# TIA_SWITCHES.net
KiCad netlist of a schematic drawn in Altium Designer
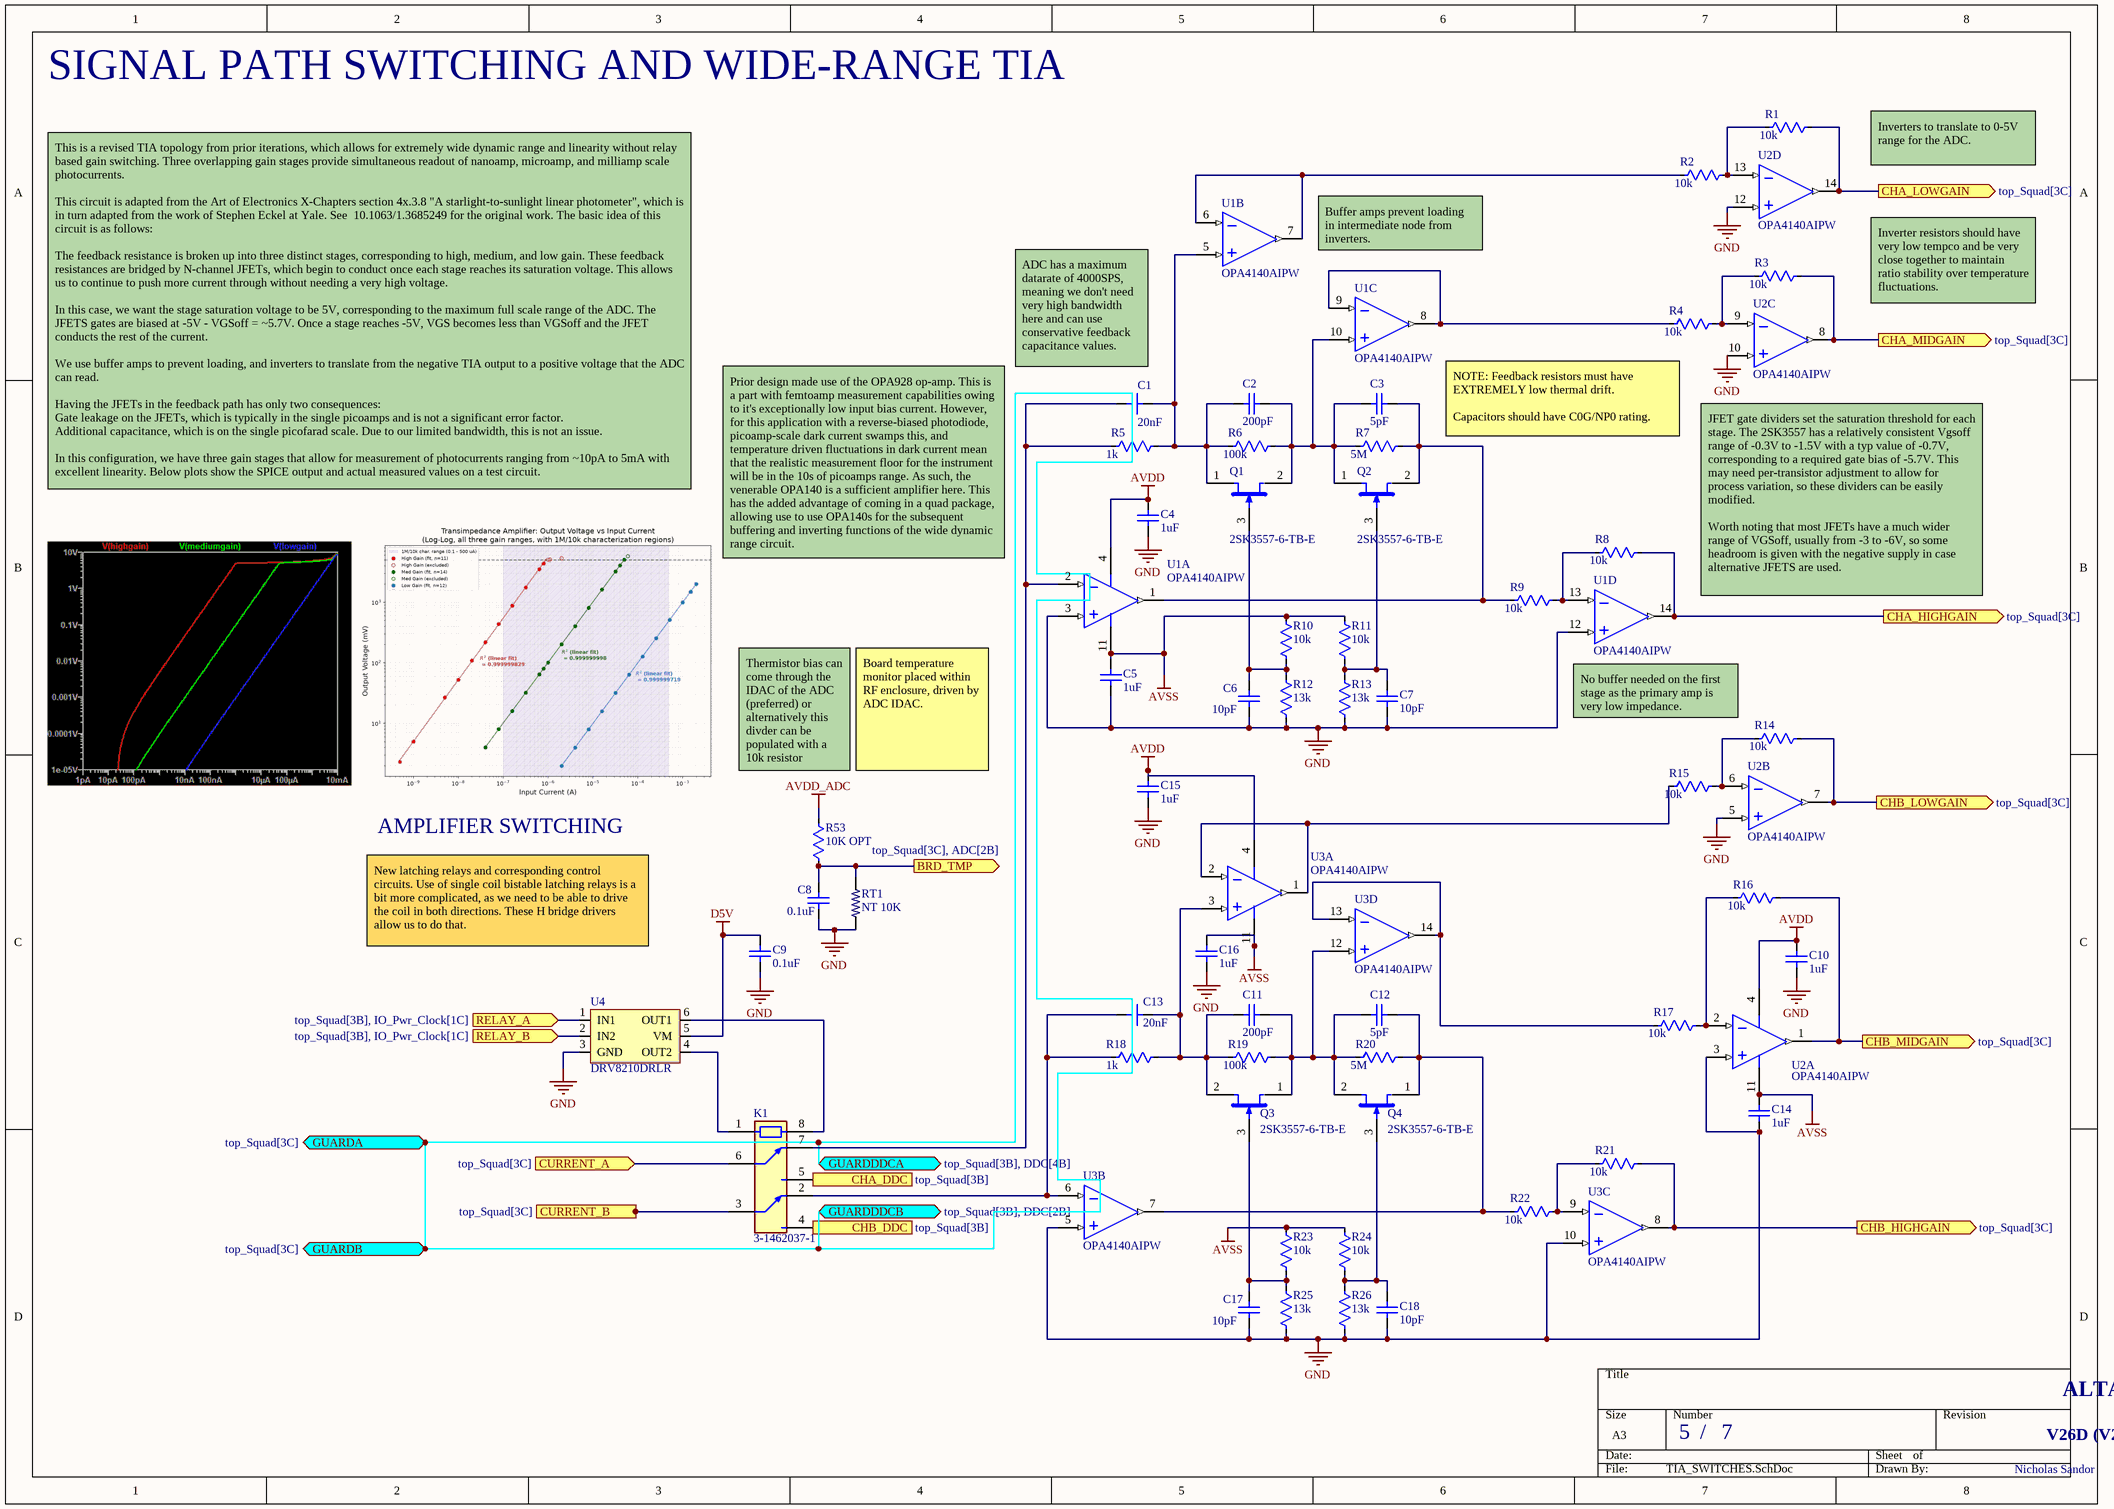
[diagram p0: TIA_SWITCHES.SchDoc]

(export (version "E")
  (design (tool "Eeschema 10.0.6"))
  (components
    (comp (ref "C1")
      (value "20nF")
      (footprint "CAP 1206 UNKNOWN")
      (description "Wurth Elektronik 885012008037 - Cap Ceramic 10pF 5% 50V NP0 1206")
      (fields (field (name "MF") "Wurth Elektronik") (field (name "MP") "885012008037"))
      (libsource (lib "ALTAIR_PD_Capacitors") (part "CAP"))
    )
    (comp (ref "C2")
      (value "200pF")
      (footprint "CAP 1206 UNKNOWN")
      (description "Wurth Elektronik 885012008037 - Cap Ceramic 10pF 5% 50V NP0 1206")
      (fields (field (name "MF") "Wurth Elektronik") (field (name "MP") "885012008037"))
      (libsource (lib "ALTAIR_PD_Capacitors") (part "CAP"))
    )
    (comp (ref "C3")
      (value "5pF")
      (footprint "CAP 1206 UNKNOWN")
      (description "Wurth Elektronik 885012008037 - Cap Ceramic 10pF 5% 50V NP0 1206")
      (fields (field (name "MF") "Wurth Elektronik") (field (name "MP") "885012008037"))
      (libsource (lib "ALTAIR_PD_Capacitors") (part "CAP"))
    )
    (comp (ref "C4")
      (value "1uF")
      (footprint "CAP 0603 IPC MID DENSITY")
      (description "Murata GRT188R61H105KE13D - Cap MLCC AEC-Q200 X5R 1uF 50V 0603")
      (fields (field (name "MF") "Murata") (field (name "MP") "GRT188R61H105KE13D"))
      (libsource (lib "ALTAIR_PD_Capacitors") (part "CAP"))
    )
    (comp (ref "C5")
      (value "1uF")
      (footprint "CAP 0603 IPC MID DENSITY")
      (description "Murata GRT188R61H105KE13D - Cap MLCC AEC-Q200 X5R 1uF 50V 0603")
      (fields (field (name "MF") "Murata") (field (name "MP") "GRT188R61H105KE13D"))
      (libsource (lib "ALTAIR_PD_Capacitors") (part "CAP"))
    )
    (comp (ref "C6")
      (value "10pF")
      (footprint "CAP 0603 IPC MID DENSITY MURATA")
      (description "Wurth Elektronik 885012008037 - Cap Ceramic 10pF 5% 50V NP0 1206")
      (fields (field (name "MF") "Wurth Elektronik") (field (name "MP") "885012008037"))
      (libsource (lib "ALTAIR_PD_Capacitors") (part "CAP"))
    )
    (comp (ref "C7")
      (value "10pF")
      (footprint "CAP 0603 IPC MID DENSITY MURATA")
      (description "Wurth Elektronik 885012008037 - Cap Ceramic 10pF 5% 50V NP0 1206")
      (fields (field (name "MF") "Wurth Elektronik") (field (name "MP") "885012008037"))
      (libsource (lib "ALTAIR_PD_Capacitors") (part "CAP"))
    )
    (comp (ref "C8")
      (value "0.1uF")
      (footprint "CAP 0603 IPC MID DENSITY")
      (description "Kemet C0603C104K5RACAUTO - Cap Ceramic 0.1uF 50V X7R 10% 0603 125C Paper T/R")
      (fields (field (name "MF") "Kemet") (field (name "MP") "C0603C104K5RACAUTO"))
      (libsource (lib "ALTAIR_PD_Capacitors") (part "CAP"))
    )
    (comp (ref "C9")
      (value "0.1uF")
      (footprint "CAP 0603 IPC MID DENSITY")
      (description "Kemet C0603C104K5RACAUTO - Cap Ceramic 0.1uF 50V X7R 10% 0603 125C Paper T/R")
      (fields (field (name "MF") "Kemet") (field (name "MP") "C0603C104K5RACAUTO"))
      (libsource (lib "ALTAIR_PD_Capacitors") (part "CAP"))
    )
    (comp (ref "C10")
      (value "1uF")
      (footprint "CAP 0603 IPC MID DENSITY")
      (description "Murata GRT188R61H105KE13D - Cap MLCC AEC-Q200 X5R 1uF 50V 0603")
      (fields (field (name "MF") "Murata") (field (name "MP") "GRT188R61H105KE13D"))
      (libsource (lib "ALTAIR_PD_Capacitors") (part "CAP"))
    )
    (comp (ref "C11")
      (value "200pF")
      (footprint "CAP 1206 UNKNOWN")
      (description "Wurth Elektronik 885012008037 - Cap Ceramic 10pF 5% 50V NP0 1206")
      (fields (field (name "MF") "Wurth Elektronik") (field (name "MP") "885012008037"))
      (libsource (lib "ALTAIR_PD_Capacitors") (part "CAP"))
    )
    (comp (ref "C12")
      (value "5pF")
      (footprint "CAP 1206 UNKNOWN")
      (description "Wurth Elektronik 885012008037 - Cap Ceramic 10pF 5% 50V NP0 1206")
      (fields (field (name "MF") "Wurth Elektronik") (field (name "MP") "885012008037"))
      (libsource (lib "ALTAIR_PD_Capacitors") (part "CAP"))
    )
    (comp (ref "C13")
      (value "20nF")
      (footprint "CAP 1206 UNKNOWN")
      (description "Wurth Elektronik 885012008037 - Cap Ceramic 10pF 5% 50V NP0 1206")
      (fields (field (name "MF") "Wurth Elektronik") (field (name "MP") "885012008037"))
      (libsource (lib "ALTAIR_PD_Capacitors") (part "CAP"))
    )
    (comp (ref "C14")
      (value "1uF")
      (footprint "CAP 0603 IPC MID DENSITY")
      (description "Murata GRT188R61H105KE13D - Cap MLCC AEC-Q200 X5R 1uF 50V 0603")
      (fields (field (name "MF") "Murata") (field (name "MP") "GRT188R61H105KE13D"))
      (libsource (lib "ALTAIR_PD_Capacitors") (part "CAP"))
    )
    (comp (ref "C15")
      (value "1uF")
      (footprint "CAP 0603 IPC MID DENSITY")
      (description "Murata GRT188R61H105KE13D - Cap MLCC AEC-Q200 X5R 1uF 50V 0603")
      (fields (field (name "MF") "Murata") (field (name "MP") "GRT188R61H105KE13D"))
      (libsource (lib "ALTAIR_PD_Capacitors") (part "CAP"))
    )
    (comp (ref "C16")
      (value "1uF")
      (footprint "CAP 0603 IPC MID DENSITY")
      (description "Murata GRT188R61H105KE13D - Cap MLCC AEC-Q200 X5R 1uF 50V 0603")
      (fields (field (name "MF") "Murata") (field (name "MP") "GRT188R61H105KE13D"))
      (libsource (lib "ALTAIR_PD_Capacitors") (part "CAP"))
    )
    (comp (ref "C17")
      (value "10pF")
      (footprint "CAP 0603 IPC MID DENSITY MURATA")
      (description "Wurth Elektronik 885012008037 - Cap Ceramic 10pF 5% 50V NP0 1206")
      (fields (field (name "MF") "Wurth Elektronik") (field (name "MP") "885012008037"))
      (libsource (lib "ALTAIR_PD_Capacitors") (part "CAP"))
    )
    (comp (ref "C18")
      (value "10pF")
      (footprint "CAP 0603 IPC MID DENSITY MURATA")
      (description "Wurth Elektronik 885012008037 - Cap Ceramic 10pF 5% 50V NP0 1206")
      (fields (field (name "MF") "Wurth Elektronik") (field (name "MP") "885012008037"))
      (libsource (lib "ALTAIR_PD_Capacitors") (part "CAP"))
    )
    (comp (ref "K1")
      (value "3-1462037-1")
      (footprint "RELAY_3-1462037-1")
      (fields (field (name "MF") "TE Connectivity"))
      (libsource (lib "ALTAIR_PD_Switches") (part "3-1462037-1"))
    )
    (comp (ref "Q1")
      (value "2SK3557-6-TB-E")
      (footprint "ONSC-CP-3-318AN_A_V")
      (description "N-Channel JFET, 15 V, 10 to 20 mA, 35 mS, 3-Pin CP, Pb-Free, Tape and Reel")
      (fields (field (name "MANUFACTURER") "On Semiconductor"))
      (libsource (lib "ALTAIR_PD_FETs") (part "CMP-1062-00010-1"))
    )
    (comp (ref "Q2")
      (value "2SK3557-6-TB-E")
      (footprint "ONSC-CP-3-318AN_A_V")
      (description "N-Channel JFET, 15 V, 10 to 20 mA, 35 mS, 3-Pin CP, Pb-Free, Tape and Reel")
      (fields (field (name "MANUFACTURER") "On Semiconductor"))
      (libsource (lib "ALTAIR_PD_FETs") (part "CMP-1062-00010-1"))
    )
    (comp (ref "Q3")
      (value "2SK3557-6-TB-E")
      (footprint "ONSC-CP-3-318AN_A_V")
      (description "N-Channel JFET, 15 V, 10 to 20 mA, 35 mS, 3-Pin CP, Pb-Free, Tape and Reel")
      (fields (field (name "MANUFACTURER") "On Semiconductor"))
      (libsource (lib "ALTAIR_PD_FETs") (part "CMP-1062-00010-1"))
    )
    (comp (ref "Q4")
      (value "2SK3557-6-TB-E")
      (footprint "ONSC-CP-3-318AN_A_V")
      (description "N-Channel JFET, 15 V, 10 to 20 mA, 35 mS, 3-Pin CP, Pb-Free, Tape and Reel")
      (fields (field (name "MANUFACTURER") "On Semiconductor"))
      (libsource (lib "ALTAIR_PD_FETs") (part "CMP-1062-00010-1"))
    )
    (comp (ref "R1")
      (value "10k")
      (footprint "RES 0603 IPC MID DENSITY")
      (description "Vishay TNPV12061M00BYEN - Res 1MOhm 0.1% 1/4W SMD 1206")
      (fields (field (name "MF") "Vishay Dale") (field (name "MP") "TNPV12061M00BYEN"))
      (libsource (lib "ALTAIR_PD_Resistors") (part "RES"))
    )
    (comp (ref "R2")
      (value "10k")
      (footprint "RES 0603 IPC MID DENSITY")
      (description "Vishay TNPV12061M00BYEN - Res 1MOhm 0.1% 1/4W SMD 1206")
      (fields (field (name "MF") "Vishay Dale") (field (name "MP") "TNPV12061M00BYEN"))
      (libsource (lib "ALTAIR_PD_Resistors") (part "RES"))
    )
    (comp (ref "R3")
      (value "10k")
      (footprint "RES 0603 IPC MID DENSITY")
      (description "Vishay TNPV12061M00BYEN - Res 1MOhm 0.1% 1/4W SMD 1206")
      (fields (field (name "MF") "Vishay Dale") (field (name "MP") "TNPV12061M00BYEN"))
      (libsource (lib "ALTAIR_PD_Resistors") (part "RES"))
    )
    (comp (ref "R4")
      (value "10k")
      (footprint "RES 0603 IPC MID DENSITY")
      (description "Vishay TNPV12061M00BYEN - Res 1MOhm 0.1% 1/4W SMD 1206")
      (fields (field (name "MF") "Vishay Dale") (field (name "MP") "TNPV12061M00BYEN"))
      (libsource (lib "ALTAIR_PD_Resistors") (part "RES"))
    )
    (comp (ref "R5")
      (value "1k")
      (footprint "RES 1206 IPC MID DENSITY")
      (description "Vishay TNPV12061M00BYEN - Res 1MOhm 0.1% 1/4W SMD 1206")
      (fields (field (name "MF") "Vishay Dale") (field (name "MP") "TNPV12061M00BYEN"))
      (libsource (lib "ALTAIR_PD_Resistors") (part "RES"))
    )
    (comp (ref "R6")
      (value "100k")
      (footprint "RES 1206 IPC MID DENSITY")
      (description "Vishay TNPV12061M00BYEN - Res 1MOhm 0.1% 1/4W SMD 1206")
      (fields (field (name "MF") "Vishay Dale") (field (name "MP") "TNPV12061M00BYEN"))
      (libsource (lib "ALTAIR_PD_Resistors") (part "RES"))
    )
    (comp (ref "R7")
      (value "5M")
      (footprint "RES 1206 IPC MID DENSITY")
      (description "Vishay TNPV12061M00BYEN - Res 1MOhm 0.1% 1/4W SMD 1206")
      (fields (field (name "MF") "Vishay Dale") (field (name "MP") "TNPV12061M00BYEN"))
      (libsource (lib "ALTAIR_PD_Resistors") (part "RES"))
    )
    (comp (ref "R8")
      (value "10k")
      (footprint "RES 0603 IPC MID DENSITY")
      (description "Vishay TNPV12061M00BYEN - Res 1MOhm 0.1% 1/4W SMD 1206")
      (fields (field (name "MF") "Vishay Dale") (field (name "MP") "TNPV12061M00BYEN"))
      (libsource (lib "ALTAIR_PD_Resistors") (part "RES"))
    )
    (comp (ref "R9")
      (value "10k")
      (footprint "RES 0603 IPC MID DENSITY")
      (description "Vishay TNPV12061M00BYEN - Res 1MOhm 0.1% 1/4W SMD 1206")
      (fields (field (name "MF") "Vishay Dale") (field (name "MP") "TNPV12061M00BYEN"))
      (libsource (lib "ALTAIR_PD_Resistors") (part "RES"))
    )
    (comp (ref "R10")
      (value "10k")
      (footprint "RES 0603 IPC MID DENSITY")
      (description "Vishay TNPV12061M00BYEN - Res 1MOhm 0.1% 1/4W SMD 1206")
      (fields (field (name "MF") "Vishay Dale") (field (name "MP") "TNPV12061M00BYEN"))
      (libsource (lib "ALTAIR_PD_Resistors") (part "RES"))
    )
    (comp (ref "R11")
      (value "10k")
      (footprint "RES 0603 IPC MID DENSITY")
      (description "Vishay TNPV12061M00BYEN - Res 1MOhm 0.1% 1/4W SMD 1206")
      (fields (field (name "MF") "Vishay Dale") (field (name "MP") "TNPV12061M00BYEN"))
      (libsource (lib "ALTAIR_PD_Resistors") (part "RES"))
    )
    (comp (ref "R12")
      (value "13k")
      (footprint "RES 0603 IPC MID DENSITY")
      (description "Vishay TNPV12061M00BYEN - Res 1MOhm 0.1% 1/4W SMD 1206")
      (fields (field (name "MF") "Vishay Dale") (field (name "MP") "TNPV12061M00BYEN"))
      (libsource (lib "ALTAIR_PD_Resistors") (part "RES"))
    )
    (comp (ref "R13")
      (value "13k")
      (footprint "RES 0603 IPC MID DENSITY")
      (description "Vishay TNPV12061M00BYEN - Res 1MOhm 0.1% 1/4W SMD 1206")
      (fields (field (name "MF") "Vishay Dale") (field (name "MP") "TNPV12061M00BYEN"))
      (libsource (lib "ALTAIR_PD_Resistors") (part "RES"))
    )
    (comp (ref "R14")
      (value "10k")
      (footprint "RES 0603 IPC MID DENSITY")
      (description "Vishay TNPV12061M00BYEN - Res 1MOhm 0.1% 1/4W SMD 1206")
      (fields (field (name "MF") "Vishay Dale") (field (name "MP") "TNPV12061M00BYEN"))
      (libsource (lib "ALTAIR_PD_Resistors") (part "RES"))
    )
    (comp (ref "R15")
      (value "10k")
      (footprint "RES 0603 IPC MID DENSITY")
      (description "Vishay TNPV12061M00BYEN - Res 1MOhm 0.1% 1/4W SMD 1206")
      (fields (field (name "MF") "Vishay Dale") (field (name "MP") "TNPV12061M00BYEN"))
      (libsource (lib "ALTAIR_PD_Resistors") (part "RES"))
    )
    (comp (ref "R16")
      (value "10k")
      (footprint "RES 0603 IPC MID DENSITY")
      (description "Vishay TNPV12061M00BYEN - Res 1MOhm 0.1% 1/4W SMD 1206")
      (fields (field (name "MF") "Vishay Dale") (field (name "MP") "TNPV12061M00BYEN"))
      (libsource (lib "ALTAIR_PD_Resistors") (part "RES"))
    )
    (comp (ref "R17")
      (value "10k")
      (footprint "RES 0603 IPC MID DENSITY")
      (description "Vishay TNPV12061M00BYEN - Res 1MOhm 0.1% 1/4W SMD 1206")
      (fields (field (name "MF") "Vishay Dale") (field (name "MP") "TNPV12061M00BYEN"))
      (libsource (lib "ALTAIR_PD_Resistors") (part "RES"))
    )
    (comp (ref "R18")
      (value "1k")
      (footprint "RES 1206 IPC MID DENSITY")
      (description "Vishay TNPV12061M00BYEN - Res 1MOhm 0.1% 1/4W SMD 1206")
      (fields (field (name "MF") "Vishay Dale") (field (name "MP") "TNPV12061M00BYEN"))
      (libsource (lib "ALTAIR_PD_Resistors") (part "RES"))
    )
    (comp (ref "R19")
      (value "100k")
      (footprint "RES 1206 IPC MID DENSITY")
      (description "Vishay TNPV12061M00BYEN - Res 1MOhm 0.1% 1/4W SMD 1206")
      (fields (field (name "MF") "Vishay Dale") (field (name "MP") "TNPV12061M00BYEN"))
      (libsource (lib "ALTAIR_PD_Resistors") (part "RES"))
    )
    (comp (ref "R20")
      (value "5M")
      (footprint "RES 1206 IPC MID DENSITY")
      (description "Vishay TNPV12061M00BYEN - Res 1MOhm 0.1% 1/4W SMD 1206")
      (fields (field (name "MF") "Vishay Dale") (field (name "MP") "TNPV12061M00BYEN"))
      (libsource (lib "ALTAIR_PD_Resistors") (part "RES"))
    )
    (comp (ref "R21")
      (value "10k")
      (footprint "RES 0603 IPC MID DENSITY")
      (description "Vishay TNPV12061M00BYEN - Res 1MOhm 0.1% 1/4W SMD 1206")
      (fields (field (name "MF") "Vishay Dale") (field (name "MP") "TNPV12061M00BYEN"))
      (libsource (lib "ALTAIR_PD_Resistors") (part "RES"))
    )
    (comp (ref "R22")
      (value "10k")
      (footprint "RES 0603 IPC MID DENSITY")
      (description "Vishay TNPV12061M00BYEN - Res 1MOhm 0.1% 1/4W SMD 1206")
      (fields (field (name "MF") "Vishay Dale") (field (name "MP") "TNPV12061M00BYEN"))
      (libsource (lib "ALTAIR_PD_Resistors") (part "RES"))
    )
    (comp (ref "R23")
      (value "10k")
      (footprint "RES 0603 IPC MID DENSITY")
      (description "Vishay TNPV12061M00BYEN - Res 1MOhm 0.1% 1/4W SMD 1206")
      (fields (field (name "MF") "Vishay Dale") (field (name "MP") "TNPV12061M00BYEN"))
      (libsource (lib "ALTAIR_PD_Resistors") (part "RES"))
    )
    (comp (ref "R24")
      (value "10k")
      (footprint "RES 0603 IPC MID DENSITY")
      (description "Vishay TNPV12061M00BYEN - Res 1MOhm 0.1% 1/4W SMD 1206")
      (fields (field (name "MF") "Vishay Dale") (field (name "MP") "TNPV12061M00BYEN"))
      (libsource (lib "ALTAIR_PD_Resistors") (part "RES"))
    )
    (comp (ref "R25")
      (value "13k")
      (footprint "RES 0603 IPC MID DENSITY")
      (description "Vishay TNPV12061M00BYEN - Res 1MOhm 0.1% 1/4W SMD 1206")
      (fields (field (name "MF") "Vishay Dale") (field (name "MP") "TNPV12061M00BYEN"))
      (libsource (lib "ALTAIR_PD_Resistors") (part "RES"))
    )
    (comp (ref "R26")
      (value "13k")
      (footprint "RES 0603 IPC MID DENSITY")
      (description "Vishay TNPV12061M00BYEN - Res 1MOhm 0.1% 1/4W SMD 1206")
      (fields (field (name "MF") "Vishay Dale") (field (name "MP") "TNPV12061M00BYEN"))
      (libsource (lib "ALTAIR_PD_Resistors") (part "RES"))
    )
    (comp (ref "R53")
      (value "10K OPT")
      (footprint "RES 0603 IPC MID DENSITY")
      (description "Yageo RC0402JR-070RL - Res 0 Ohms 1/16W SMD 0402")
      (fields (field (name "MF") "YAGEO") (field (name "MP") "RC0402JR-070RL"))
      (libsource (lib "ALTAIR_PD_Resistors") (part "RES"))
    )
    (comp (ref "RT1")
      (value "NT 10K")
      (footprint "RES 0603 IPC MID DENSITY")
      (description "THERMISTOR NTC 10KOHM 3380K 0603")
      (fields (field (name "MF") "Murata") (field (name "MP") "NCU18XH103F60RB"))
      (libsource (lib "ALTAIR_PD_Resistors") (part "THERM_RES NTC 0603 10K 1%"))
    )
    (comp (ref "U1")
      (value "OPA4140AIPW")
      (footprint "PW0014A_N")
      (fields (field (name "MANUFACTURER") "Texas Instruments"))
      (libsource (lib "ALTAIR_PD_Amplifiers") (part "CMP-0272-01663-3"))
    )
    (comp (ref "U2")
      (value "OPA4140AIPW")
      (footprint "PW0014A_N")
      (fields (field (name "MANUFACTURER") "Texas Instruments"))
      (libsource (lib "ALTAIR_PD_Amplifiers") (part "CMP-0272-01663-3"))
    )
    (comp (ref "U3")
      (value "OPA4140AIPW")
      (footprint "PW0014A_N")
      (fields (field (name "MANUFACTURER") "Texas Instruments"))
      (libsource (lib "ALTAIR_PD_Amplifiers") (part "CMP-0272-01663-3"))
    )
    (comp (ref "U4")
      (value "DRV8210DRLR")
      (footprint "SOT563")
      (description "Bipolar Motor Driver NMOS PWM SOT-563")
      (libsource (lib "ALTAIR_PD_DigitalLogic") (part "DRV8210DRLR"))
    )
  )
  (nets
    (net (code "1") (name "/BRD_TMP") (class "Default")
      (node (ref "C8") (pin "2") (pinfunction "2_2") (pintype "passive"))
      (node (ref "R53") (pin "2") (pinfunction "2_2") (pintype "passive"))
      (node (ref "RT1") (pin "2") (pintype "passive"))
    )
    (net (code "2") (name "/CHA_DDC") (class "Default")
      (node (ref "K1") (pin "5") (pinfunction "NO1_5") (pintype "passive"))
    )
    (net (code "3") (name "/CHA_HIGHGAIN") (class "Default")
      (node (ref "R8") (pin "2") (pinfunction "2_2") (pintype "passive"))
      (node (ref "U1") (pin "14") (pinfunction "OUT_D_14") (pintype "output"))
    )
    (net (code "4") (name "/CHA_LOWGAIN") (class "Default")
      (node (ref "R1") (pin "2") (pinfunction "2_2") (pintype "passive"))
      (node (ref "U2") (pin "14") (pinfunction "OUT_D_14") (pintype "output"))
    )
    (net (code "5") (name "/CHA_MIDGAIN") (class "Default")
      (node (ref "R3") (pin "2") (pinfunction "2_2") (pintype "passive"))
      (node (ref "U2") (pin "8") (pinfunction "OUT_C_8") (pintype "output"))
    )
    (net (code "6") (name "/CHB_DDC") (class "Default")
      (node (ref "K1") (pin "4") (pinfunction "NO2_4") (pintype "passive"))
    )
    (net (code "7") (name "/CHB_HIGHGAIN") (class "Default")
      (node (ref "R21") (pin "2") (pinfunction "2_2") (pintype "passive"))
      (node (ref "U3") (pin "8") (pinfunction "OUT_C_8") (pintype "output"))
    )
    (net (code "8") (name "/CHB_LOWGAIN") (class "Default")
      (node (ref "R14") (pin "2") (pinfunction "2_2") (pintype "passive"))
      (node (ref "U2") (pin "7") (pinfunction "OUT_B_7") (pintype "output"))
    )
    (net (code "9") (name "/CHB_MIDGAIN") (class "Default")
      (node (ref "R16") (pin "2") (pinfunction "2_2") (pintype "passive"))
      (node (ref "U2") (pin "1") (pinfunction "OUT_A_1") (pintype "output"))
    )
    (net (code "10") (name "/CURRENT_A") (class "Default")
      (node (ref "K1") (pin "6") (pinfunction "COM1_6") (pintype "passive"))
    )
    (net (code "11") (name "/CURRENT_B") (class "Default")
      (node (ref "K1") (pin "3") (pinfunction "COM2_3") (pintype "passive"))
    )
    (net (code "13") (name "/RELAY_A") (class "Default")
      (node (ref "U4") (pin "1") (pinfunction "IN1_1") (pintype "passive"))
    )
    (net (code "14") (name "/RELAY_B") (class "Default")
      (node (ref "U4") (pin "2") (pinfunction "IN2_2") (pintype "passive"))
    )
    (net (code "15") (name "AVDD") (class "Default")
      (node (ref "C10") (pin "2") (pinfunction "2_2") (pintype "passive"))
      (node (ref "C15") (pin "2") (pinfunction "2_2") (pintype "passive"))
      (node (ref "C4") (pin "2") (pinfunction "2_2") (pintype "passive"))
      (node (ref "U1") (pin "4") (pinfunction "V+_4") (pintype "power_in"))
      (node (ref "U2") (pin "4") (pinfunction "V+_4") (pintype "power_in"))
      (node (ref "U3") (pin "4") (pinfunction "V+_4") (pintype "power_in"))
    )
    (net (code "16") (name "AVDD_ADC") (class "Default")
      (node (ref "R53") (pin "1") (pinfunction "1_1") (pintype "passive"))
    )
    (net (code "17") (name "AVSS") (class "Default")
      (node (ref "C14") (pin "2") (pinfunction "2_2") (pintype "passive"))
      (node (ref "C16") (pin "2") (pinfunction "2_2") (pintype "passive"))
      (node (ref "C5") (pin "2") (pinfunction "2_2") (pintype "passive"))
      (node (ref "R10") (pin "2") (pinfunction "2_2") (pintype "passive"))
      (node (ref "R11") (pin "2") (pinfunction "2_2") (pintype "passive"))
      (node (ref "R23") (pin "2") (pinfunction "2_2") (pintype "passive"))
      (node (ref "R24") (pin "2") (pinfunction "2_2") (pintype "passive"))
      (node (ref "U1") (pin "11") (pinfunction "V-_11") (pintype "power_in"))
      (node (ref "U2") (pin "11") (pinfunction "V-_11") (pintype "power_in"))
      (node (ref "U3") (pin "11") (pinfunction "V-_11") (pintype "power_in"))
    )
    (net (code "18") (name "D5V") (class "Default")
      (node (ref "C9") (pin "2") (pinfunction "2_2") (pintype "passive"))
      (node (ref "U4") (pin "5") (pinfunction "VM_5") (pintype "power_in"))
    )
    (net (code "19") (name "GND") (class "Default")
      (node (ref "C10") (pin "1") (pinfunction "1_1") (pintype "passive"))
      (node (ref "C14") (pin "1") (pinfunction "1_1") (pintype "passive"))
      (node (ref "C15") (pin "1") (pinfunction "1_1") (pintype "passive"))
      (node (ref "C16") (pin "1") (pinfunction "1_1") (pintype "passive"))
      (node (ref "C17") (pin "1") (pinfunction "1_1") (pintype "passive"))
      (node (ref "C18") (pin "1") (pinfunction "1_1") (pintype "passive"))
      (node (ref "C4") (pin "1") (pinfunction "1_1") (pintype "passive"))
      (node (ref "C5") (pin "1") (pinfunction "1_1") (pintype "passive"))
      (node (ref "C6") (pin "1") (pinfunction "1_1") (pintype "passive"))
      (node (ref "C7") (pin "1") (pinfunction "1_1") (pintype "passive"))
      (node (ref "C8") (pin "1") (pinfunction "1_1") (pintype "passive"))
      (node (ref "C9") (pin "1") (pinfunction "1_1") (pintype "passive"))
      (node (ref "R12") (pin "1") (pinfunction "1_1") (pintype "passive"))
      (node (ref "R13") (pin "1") (pinfunction "1_1") (pintype "passive"))
      (node (ref "R25") (pin "1") (pinfunction "1_1") (pintype "passive"))
      (node (ref "R26") (pin "1") (pinfunction "1_1") (pintype "passive"))
      (node (ref "RT1") (pin "1") (pintype "passive"))
      (node (ref "U1") (pin "12") (pinfunction "IN_D+_12") (pintype "input"))
      (node (ref "U1") (pin "3") (pinfunction "IN_A+_3") (pintype "input"))
      (node (ref "U2") (pin "10") (pinfunction "IN_C+_10") (pintype "input"))
      (node (ref "U2") (pin "12") (pinfunction "IN_D+_12") (pintype "input"))
      (node (ref "U2") (pin "3") (pinfunction "IN_A+_3") (pintype "input"))
      (node (ref "U2") (pin "5") (pinfunction "IN_B+_5") (pintype "input"))
      (node (ref "U3") (pin "10") (pinfunction "IN_C+_10") (pintype "input"))
      (node (ref "U3") (pin "5") (pinfunction "IN_B+_5") (pintype "input"))
      (node (ref "U4") (pin "3") (pinfunction "GND_3") (pintype "power_in"))
    )
    (net (code "20") (name "Net-(K1-COIL1)") (class "Default")
      (node (ref "K1") (pin "1") (pinfunction "COIL1_1") (pintype "passive"))
      (node (ref "U4") (pin "4") (pinfunction "OUT2_4") (pintype "passive"))
    )
    (net (code "21") (name "Net-(K1-COIL2)") (class "Default")
      (node (ref "K1") (pin "8") (pinfunction "COIL2_8") (pintype "passive"))
      (node (ref "U4") (pin "6") (pinfunction "OUT1_6") (pintype "passive"))
    )
    (net (code "22") (name "Net-(K1-NC1)") (class "Default")
      (node (ref "C1") (pin "2") (pinfunction "2_2") (pintype "passive"))
      (node (ref "K1") (pin "7") (pinfunction "NC1_7") (pintype "passive"))
      (node (ref "R5") (pin "1") (pinfunction "1_1") (pintype "passive"))
      (node (ref "U1") (pin "2") (pinfunction "IN_A-_2") (pintype "input"))
    )
    (net (code "23") (name "Net-(K1-NC2)") (class "Default")
      (node (ref "C13") (pin "2") (pinfunction "2_2") (pintype "passive"))
      (node (ref "K1") (pin "2") (pinfunction "NC2_2") (pintype "passive"))
      (node (ref "R18") (pin "1") (pinfunction "1_1") (pintype "passive"))
      (node (ref "U3") (pin "6") (pinfunction "IN_B-_6") (pintype "input"))
    )
    (net (code "24") (name "Net-(Q1-D)") (class "Default")
      (node (ref "C2") (pin "1") (pinfunction "1_1") (pintype "passive"))
      (node (ref "C3") (pin "2") (pinfunction "2_2") (pintype "passive"))
      (node (ref "Q1") (pin "2") (pinfunction "D_2") (pintype "passive"))
      (node (ref "Q2") (pin "1") (pinfunction "S_1") (pintype "passive"))
      (node (ref "R6") (pin "2") (pinfunction "2_2") (pintype "passive"))
      (node (ref "R7") (pin "1") (pinfunction "1_1") (pintype "passive"))
      (node (ref "U1") (pin "10") (pinfunction "IN_C+_10") (pintype "input"))
    )
    (net (code "25") (name "Net-(Q1-G)") (class "Default")
      (node (ref "C6") (pin "2") (pinfunction "2_2") (pintype "passive"))
      (node (ref "Q1") (pin "3") (pinfunction "G_3") (pintype "passive"))
      (node (ref "R10") (pin "1") (pinfunction "1_1") (pintype "passive"))
      (node (ref "R12") (pin "2") (pinfunction "2_2") (pintype "passive"))
    )
    (net (code "26") (name "Net-(Q1-S)") (class "Default")
      (node (ref "C1") (pin "1") (pinfunction "1_1") (pintype "passive"))
      (node (ref "C2") (pin "2") (pinfunction "2_2") (pintype "passive"))
      (node (ref "Q1") (pin "1") (pinfunction "S_1") (pintype "passive"))
      (node (ref "R5") (pin "2") (pinfunction "2_2") (pintype "passive"))
      (node (ref "R6") (pin "1") (pinfunction "1_1") (pintype "passive"))
      (node (ref "U1") (pin "5") (pinfunction "IN_B+_5") (pintype "input"))
    )
    (net (code "27") (name "Net-(Q2-D)") (class "Default")
      (node (ref "C3") (pin "1") (pinfunction "1_1") (pintype "passive"))
      (node (ref "Q2") (pin "2") (pinfunction "D_2") (pintype "passive"))
      (node (ref "R7") (pin "2") (pinfunction "2_2") (pintype "passive"))
      (node (ref "R9") (pin "1") (pinfunction "1_1") (pintype "passive"))
      (node (ref "U1") (pin "1") (pinfunction "OUT_A_1") (pintype "output"))
    )
    (net (code "28") (name "Net-(Q2-G)") (class "Default")
      (node (ref "C7") (pin "2") (pinfunction "2_2") (pintype "passive"))
      (node (ref "Q2") (pin "3") (pinfunction "G_3") (pintype "passive"))
      (node (ref "R11") (pin "1") (pinfunction "1_1") (pintype "passive"))
      (node (ref "R13") (pin "2") (pinfunction "2_2") (pintype "passive"))
    )
    (net (code "29") (name "Net-(Q3-D)") (class "Default")
      (node (ref "C11") (pin "2") (pinfunction "2_2") (pintype "passive"))
      (node (ref "C13") (pin "1") (pinfunction "1_1") (pintype "passive"))
      (node (ref "Q3") (pin "2") (pinfunction "D_2") (pintype "passive"))
      (node (ref "R18") (pin "2") (pinfunction "2_2") (pintype "passive"))
      (node (ref "R19") (pin "1") (pinfunction "1_1") (pintype "passive"))
      (node (ref "U3") (pin "3") (pinfunction "IN_A+_3") (pintype "input"))
    )
    (net (code "30") (name "Net-(Q3-G)") (class "Default")
      (node (ref "C17") (pin "2") (pinfunction "2_2") (pintype "passive"))
      (node (ref "Q3") (pin "3") (pinfunction "G_3") (pintype "passive"))
      (node (ref "R23") (pin "1") (pinfunction "1_1") (pintype "passive"))
      (node (ref "R25") (pin "2") (pinfunction "2_2") (pintype "passive"))
    )
    (net (code "31") (name "Net-(Q3-S)") (class "Default")
      (node (ref "C11") (pin "1") (pinfunction "1_1") (pintype "passive"))
      (node (ref "C12") (pin "2") (pinfunction "2_2") (pintype "passive"))
      (node (ref "Q3") (pin "1") (pinfunction "S_1") (pintype "passive"))
      (node (ref "Q4") (pin "2") (pinfunction "D_2") (pintype "passive"))
      (node (ref "R19") (pin "2") (pinfunction "2_2") (pintype "passive"))
      (node (ref "R20") (pin "1") (pinfunction "1_1") (pintype "passive"))
      (node (ref "U3") (pin "12") (pinfunction "IN_D+_12") (pintype "input"))
    )
    (net (code "32") (name "Net-(Q4-G)") (class "Default")
      (node (ref "C18") (pin "2") (pinfunction "2_2") (pintype "passive"))
      (node (ref "Q4") (pin "3") (pinfunction "G_3") (pintype "passive"))
      (node (ref "R24") (pin "1") (pinfunction "1_1") (pintype "passive"))
      (node (ref "R26") (pin "2") (pinfunction "2_2") (pintype "passive"))
    )
    (net (code "33") (name "Net-(Q4-S)") (class "Default")
      (node (ref "C12") (pin "1") (pinfunction "1_1") (pintype "passive"))
      (node (ref "Q4") (pin "1") (pinfunction "S_1") (pintype "passive"))
      (node (ref "R20") (pin "2") (pinfunction "2_2") (pintype "passive"))
      (node (ref "R22") (pin "1") (pinfunction "1_1") (pintype "passive"))
      (node (ref "U3") (pin "7") (pinfunction "OUT_B_7") (pintype "output"))
    )
    (net (code "34") (name "Net-(U1B-IN_B-)") (class "Default")
      (node (ref "R2") (pin "1") (pinfunction "1_1") (pintype "passive"))
      (node (ref "U1") (pin "6") (pinfunction "IN_B-_6") (pintype "input"))
      (node (ref "U1") (pin "7") (pinfunction "OUT_B_7") (pintype "output"))
    )
    (net (code "35") (name "Net-(U1C-IN_C-)") (class "Default")
      (node (ref "R4") (pin "1") (pinfunction "1_1") (pintype "passive"))
      (node (ref "U1") (pin "8") (pinfunction "OUT_C_8") (pintype "output"))
      (node (ref "U1") (pin "9") (pinfunction "IN_C-_9") (pintype "input"))
    )
    (net (code "36") (name "Net-(U1D-IN_D-)") (class "Default")
      (node (ref "R8") (pin "1") (pinfunction "1_1") (pintype "passive"))
      (node (ref "R9") (pin "2") (pinfunction "2_2") (pintype "passive"))
      (node (ref "U1") (pin "13") (pinfunction "IN_D-_13") (pintype "input"))
    )
    (net (code "37") (name "Net-(U2A-IN_A-)") (class "Default")
      (node (ref "R16") (pin "1") (pinfunction "1_1") (pintype "passive"))
      (node (ref "R17") (pin "2") (pinfunction "2_2") (pintype "passive"))
      (node (ref "U2") (pin "2") (pinfunction "IN_A-_2") (pintype "input"))
    )
    (net (code "38") (name "Net-(U2B-IN_B-)") (class "Default")
      (node (ref "R14") (pin "1") (pinfunction "1_1") (pintype "passive"))
      (node (ref "R15") (pin "2") (pinfunction "2_2") (pintype "passive"))
      (node (ref "U2") (pin "6") (pinfunction "IN_B-_6") (pintype "input"))
    )
    (net (code "39") (name "Net-(U2C-IN_C-)") (class "Default")
      (node (ref "R3") (pin "1") (pinfunction "1_1") (pintype "passive"))
      (node (ref "R4") (pin "2") (pinfunction "2_2") (pintype "passive"))
      (node (ref "U2") (pin "9") (pinfunction "IN_C-_9") (pintype "input"))
    )
    (net (code "40") (name "Net-(U2D-IN_D-)") (class "Default")
      (node (ref "R1") (pin "1") (pinfunction "1_1") (pintype "passive"))
      (node (ref "R2") (pin "2") (pinfunction "2_2") (pintype "passive"))
      (node (ref "U2") (pin "13") (pinfunction "IN_D-_13") (pintype "input"))
    )
    (net (code "41") (name "Net-(U3A-IN_A-)") (class "Default")
      (node (ref "R15") (pin "1") (pinfunction "1_1") (pintype "passive"))
      (node (ref "U3") (pin "1") (pinfunction "OUT_A_1") (pintype "output"))
      (node (ref "U3") (pin "2") (pinfunction "IN_A-_2") (pintype "input"))
    )
    (net (code "42") (name "Net-(U3C-IN_C-)") (class "Default")
      (node (ref "R21") (pin "1") (pinfunction "1_1") (pintype "passive"))
      (node (ref "R22") (pin "2") (pinfunction "2_2") (pintype "passive"))
      (node (ref "U3") (pin "9") (pinfunction "IN_C-_9") (pintype "input"))
    )
    (net (code "43") (name "Net-(U3D-IN_D-)") (class "Default")
      (node (ref "R17") (pin "1") (pinfunction "1_1") (pintype "passive"))
      (node (ref "U3") (pin "13") (pinfunction "IN_D-_13") (pintype "input"))
      (node (ref "U3") (pin "14") (pinfunction "OUT_D_14") (pintype "output"))
    )
  )
)
